# IPM_Circuit.net
KiCad netlist of a schematic drawn in Altium Designer
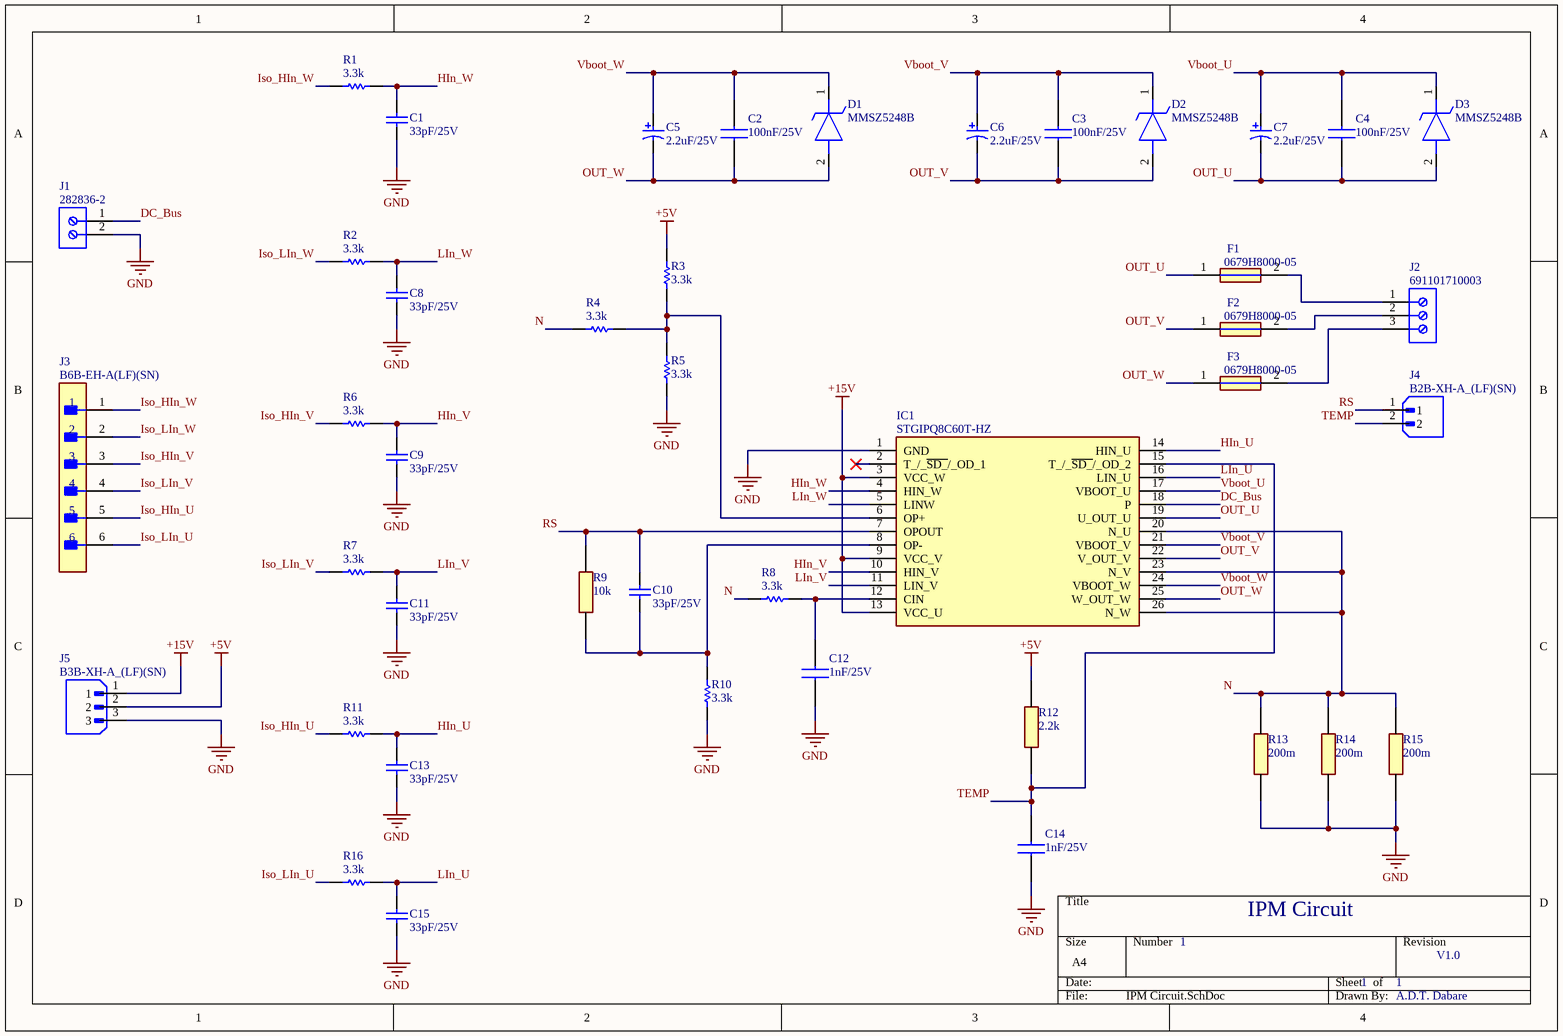
[diagram p0: IPM Circuit.SchDoc]

(export (version "E")
  (design (tool "Eeschema 10.0.6"))
  (components
    (comp (ref "C1")
      (value "33pF/25V")
      (footprint "CAPC1210(3225)100_N")
      (description "CAP 33pF 50V ±5% 1210 (3225 Metric) Thickness 1mm SMD")
      (fields (field (name "TOLERANCE") "Â±5%"))
      (libsource (lib "Altium Content Vault") (part "CAP"))
    )
    (comp (ref "C2")
      (value "100nF/25V")
      (footprint "SamacSys:CAPC3225X105N")
      (description "100nF 25V 1210 SMDCapacitor")
      (fields
        (field (name "MANUFACTURER_PART_NUMBER") "885012209015")
        (field (name "MOUSER PART NUMBER") "710-885012209015")
      )
      (libsource (lib "*") (part "885012209015"))
    )
    (comp (ref "C3")
      (value "100nF/25V")
      (footprint "SamacSys:CAPC3225X105N")
      (description "1nF 25V 1210 SMDCapacitor")
      (fields
        (field (name "MANUFACTURER_PART_NUMBER") "885012209015")
        (field (name "MOUSER PART NUMBER") "710-885012209015")
      )
      (libsource (lib "*") (part "885012209015"))
    )
    (comp (ref "C4")
      (value "100nF/25V")
      (footprint "SamacSys:CAPC3225X105N")
      (description "1nF 25V 1210 SMDCapacitor")
      (fields
        (field (name "MANUFACTURER_PART_NUMBER") "885012209015")
        (field (name "MOUSER PART NUMBER") "710-885012209015")
      )
      (libsource (lib "*") (part "885012209015"))
    )
    (comp (ref "C5")
      (value "2.2uF/25V")
      (footprint "CAPPR55-200-1100X500X1200")
      (description "Aluminum Electrolytic Capacitor, 2.2 uF, +/- 20%, 50 V, -40 to 85 degC, 2-Pin THD, RoHS, Bulk")
      (fields (field (name "VOLTAGE") "50V") (field (name "MANUFACTURER") "Panasonic"))
      (libsource (lib "Altium Content Vault") (part "CAP-P-2"))
    )
    (comp (ref "C6")
      (value "2.2uF/25V")
      (footprint "CAPPR55-200-1100X500X1200")
      (description "Aluminum Electrolytic Capacitor, 2.2 uF, +/- 20%, 50 V, -40 to 85 degC, 2-Pin THD, RoHS, Bulk")
      (fields (field (name "VOLTAGE") "50V") (field (name "MANUFACTURER") "Panasonic"))
      (libsource (lib "Altium Content Vault") (part "CAP-P-2"))
    )
    (comp (ref "C7")
      (value "2.2uF/25V")
      (footprint "CAPPR55-200-1100X500X1200")
      (description "Aluminum Electrolytic Capacitor, 2.2 uF, +/- 20%, 50 V, -40 to 85 degC, 2-Pin THD, RoHS, Bulk")
      (fields (field (name "VOLTAGE") "50V") (field (name "MANUFACTURER") "Panasonic"))
      (libsource (lib "Altium Content Vault") (part "CAP-P-2"))
    )
    (comp (ref "C8")
      (value "33pF/25V")
      (footprint "CAPC1210(3225)100_N")
      (description "CAP 33pF 50V ±5% 1210 (3225 Metric) Thickness 1mm SMD")
      (fields (field (name "TOLERANCE") "Â±5%"))
      (libsource (lib "Altium Content Vault") (part "CAP"))
    )
    (comp (ref "C9")
      (value "33pF/25V")
      (footprint "CAPC1210(3225)100_N")
      (description "CAP 33pF 50V ±5% 1210 (3225 Metric) Thickness 1mm SMD")
      (fields (field (name "TOLERANCE") "Â±5%"))
      (libsource (lib "Altium Content Vault") (part "CAP"))
    )
    (comp (ref "C10")
      (value "33pF/25V")
      (footprint "CAPC1210(3225)100_N")
      (description "CAP 33pF 50V ±5% 1210 (3225 Metric) Thickness 1mm SMD")
      (fields (field (name "TOLERANCE") "Â±5%"))
      (libsource (lib "Altium Content Vault") (part "CAP"))
    )
    (comp (ref "C11")
      (value "33pF/25V")
      (footprint "CAPC1210(3225)100_N")
      (description "CAP 33pF 50V ±5% 1210 (3225 Metric) Thickness 1mm SMD")
      (fields (field (name "TOLERANCE") "Â±5%"))
      (libsource (lib "Altium Content Vault") (part "CAP"))
    )
    (comp (ref "C12")
      (value "1nF/25V")
      (footprint "SamacSys:CAPC3225X105N")
      (description "1nF 25V 1210 SMDCapacitor")
      (fields
        (field (name "MANUFACTURER_PART_NUMBER") "885012209015")
        (field (name "MOUSER PART NUMBER") "710-885012209015")
      )
      (libsource (lib "*") (part "885012209015"))
    )
    (comp (ref "C13")
      (value "33pF/25V")
      (footprint "CAPC1210(3225)100_N")
      (description "CAP 33pF 50V ±5% 1210 (3225 Metric) Thickness 1mm SMD")
      (fields (field (name "TOLERANCE") "Â±5%"))
      (libsource (lib "Altium Content Vault") (part "CAP"))
    )
    (comp (ref "C14")
      (value "1nF/25V")
      (footprint "SamacSys:CAPC3225X105N")
      (description "1nF 25V 1210 SMDCapacitor")
      (fields
        (field (name "MANUFACTURER_PART_NUMBER") "885012209015")
        (field (name "MOUSER PART NUMBER") "710-885012209015")
      )
      (libsource (lib "*") (part "885012209015"))
    )
    (comp (ref "C15")
      (value "33pF/25V")
      (footprint "CAPC1210(3225)100_N")
      (description "CAP 33pF 50V ±5% 1210 (3225 Metric) Thickness 1mm SMD")
      (fields (field (name "TOLERANCE") "Â±5%"))
      (libsource (lib "Altium Content Vault") (part "CAP"))
    )
    (comp (ref "D1")
      (value "MMSZ5248B")
      (footprint "SamacSys:SOD3816X135N")
      (description "Diode")
      (fields
        (field (name "MANUFACTURER_PART_NUMBER") "MMSZ5248B_R1_00001")
        (field (name "MOUSER PART NUMBER") "241-MMSZ5248BR100001")
      )
      (libsource (lib "SamacSys") (part "MMSZ5248B_R1_00001"))
    )
    (comp (ref "D2")
      (value "MMSZ5248B")
      (footprint "SamacSys:SOD3816X135N")
      (description "Diode")
      (fields
        (field (name "MANUFACTURER_PART_NUMBER") "MMSZ5248B_R1_00001")
        (field (name "MOUSER PART NUMBER") "241-MMSZ5248BR100001")
      )
      (libsource (lib "SamacSys") (part "MMSZ5248B_R1_00001"))
    )
    (comp (ref "D3")
      (value "MMSZ5248B")
      (footprint "SamacSys:SOD3816X135N")
      (description "Diode")
      (fields
        (field (name "MANUFACTURER_PART_NUMBER") "MMSZ5248B_R1_00001")
        (field (name "MOUSER PART NUMBER") "241-MMSZ5248BR100001")
      )
      (libsource (lib "SamacSys") (part "MMSZ5248B_R1_00001"))
    )
    (comp (ref "F1")
      (value "0679H8000-05")
      (footprint "SamacSys:FUSC6125X279N")
      (description "Fuse")
      (libsource (lib "*") (part "0679H8000-05"))
    )
    (comp (ref "F2")
      (value "0679H8000-05")
      (footprint "SamacSys:FUSC6125X279N")
      (description "Fuse")
      (libsource (lib "*") (part "0679H8000-05"))
    )
    (comp (ref "F3")
      (value "0679H8000-05")
      (footprint "SamacSys:FUSC6125X279N")
      (description "Fuse")
      (libsource (lib "*") (part "0679H8000-05"))
    )
    (comp (ref "IC1")
      (value "STGIPQ8C60T-HZ")
      (footprint "SamacSys:STGIPQ5C60THZS")
      (description "Integrated Circuit")
      (fields (field (name "MOUSER PART NUMBER") "511-STGIPQ8C60T-HZ"))
      (libsource (lib "*") (part "STGIPQ8C60T-HZ"))
    )
    (comp (ref "J1")
      (value "282836-2")
      (footprint "TECO-282836-2_V")
      (description "Female Header, Pitch 5 mm, 1 x 2 Position, Height 10 mm, Tail Length 3.5 mm, Rohs, Bulk")
      (fields (field (name "VOLTAGE") "300V") (field (name "MANUFACTURER") "TE Connectivity"))
      (libsource (lib "Altium Content Vault") (part "CN-1P-F-TB2"))
    )
    (comp (ref "J2")
      (value "691101710003")
      (footprint "691101710003")
      (fields (field (name "VOLTAGE") "250V"))
      (libsource (lib "Altium Content Vault") (part "TBL - 1R - 03P - Screw"))
    )
    (comp (ref "J3")
      (value "B6B-EH-A(LF)(SN)")
      (footprint "FP-B6B-EH-A_LF_SN-MFG")
      (description "CONN HEADER VERT 6POS 2.5MM")
      (libsource (lib "Altium Content Vault") (part "f2cb566baf1c37ab5a3b8e90bbeafd6"))
    )
    (comp (ref "J4")
      (value "B2B-XH-A_(LF)(SN)")
      (footprint "JST_B2B-XH-A_(LF)(SN)")
      (description "Connector Header Through Hole 2 position 0.098 (2.50mm)")
      (fields (field (name "MF") "JST Sales") (field (name "MP") "B2B-XH-A (LF)(SN)"))
      (libsource (lib "B2B-XH-A__LF__SN_") (part "B2B-XH-A_(LF)(SN)"))
    )
    (comp (ref "J5")
      (value "B3B-XH-A_(LF)(SN)")
      (footprint "JST_B3B-XH-A (LF)(SN)")
      (description "Connector Header Through Hole 3 position 0.098 (2.50mm)")
      (fields (field (name "MF") "JST Sales America Inc.") (field (name "MP") "B3B-XH-A (LF)(SN)"))
      (libsource (lib "B3B-XH-A__LF__SN_") (part "B3B-XH-A_(LF)(SN)"))
    )
    (comp (ref "R1")
      (value "3.3k")
      (footprint "RESC3225X70X50NL20T20")
      (description "3.3k 0.5W 1210 SMD Resistor")
      (fields (field (name "PART NUMBER") "ERJ-L14KF10CU") (field (name "MANUFACTURER") "Panasonic"))
      (libsource (lib "Altium Content Vault") (part "RES"))
    )
    (comp (ref "R2")
      (value "3.3k")
      (footprint "RESC3225X70X50NL20T20")
      (description "3.3k 0.5W 1210 SMD Resistor")
      (fields (field (name "PART NUMBER") "ERJ-L14KF10CU") (field (name "MANUFACTURER") "Panasonic"))
      (libsource (lib "Altium Content Vault") (part "RES"))
    )
    (comp (ref "R3")
      (value "3.3k")
      (footprint "RESC3225X70X50NL20T20")
      (description "3.3k 0.5W 1210 SMD Resistor")
      (fields (field (name "PART NUMBER") "ERJ-L14KF10CU") (field (name "MANUFACTURER") "Panasonic"))
      (libsource (lib "Altium Content Vault") (part "RES"))
    )
    (comp (ref "R4")
      (value "3.3k")
      (footprint "RESC3225X70X50NL20T20")
      (description "3.3k 0.5W 1210 SMD Resistor")
      (fields (field (name "PART NUMBER") "ERJ-L14KF10CU") (field (name "MANUFACTURER") "Panasonic"))
      (libsource (lib "Altium Content Vault") (part "RES"))
    )
    (comp (ref "R5")
      (value "3.3k")
      (footprint "RESC3225X70X50NL20T20")
      (description "3.3k 0.5W 1210 SMD Resistor")
      (fields (field (name "PART NUMBER") "ERJ-L14KF10CU") (field (name "MANUFACTURER") "Panasonic"))
      (libsource (lib "Altium Content Vault") (part "RES"))
    )
    (comp (ref "R6")
      (value "3.3k")
      (footprint "RESC3225X70X50NL20T20")
      (description "3.3k 0.5W 1210 SMD Resistor")
      (fields (field (name "PART NUMBER") "ERJ-L14KF10CU") (field (name "MANUFACTURER") "Panasonic"))
      (libsource (lib "Altium Content Vault") (part "RES"))
    )
    (comp (ref "R7")
      (value "3.3k")
      (footprint "RESC3225X70X50NL20T20")
      (description "3.3k 0.5W 1210 SMD Resistor")
      (fields (field (name "PART NUMBER") "ERJ-L14KF10CU") (field (name "MANUFACTURER") "Panasonic"))
      (libsource (lib "Altium Content Vault") (part "RES"))
    )
    (comp (ref "R8")
      (value "3.3k")
      (footprint "RESC3225X70X50NL20T20")
      (description "3.3k 0.5W 1210 SMD Resistor")
      (fields (field (name "PART NUMBER") "ERJ-L14KF10CU") (field (name "MANUFACTURER") "Panasonic"))
      (libsource (lib "Altium Content Vault") (part "RES"))
    )
    (comp (ref "R9")
      (value "10k")
      (footprint "SamacSys:ERJ14BQF1R0U")
      (description "10k 0.5W 1210 SMD Resistor")
      (fields
        (field (name "MANUFACTURER_PART_NUMBER") "ERJ-14NF1002U")
        (field (name "MOUSER PART NUMBER") "667-ERJ-14NF1002U")
      )
      (libsource (lib "*") (part "ERJ-14NF1002U"))
    )
    (comp (ref "R10")
      (value "3.3k")
      (footprint "RESC3225X70X50NL20T20")
      (description "3.3k 0.5W 1210 SMD Resistor")
      (fields (field (name "PART NUMBER") "ERJ-L14KF10CU") (field (name "MANUFACTURER") "Panasonic"))
      (libsource (lib "Altium Content Vault") (part "RES"))
    )
    (comp (ref "R11")
      (value "3.3k")
      (footprint "RESC3225X70X50NL20T20")
      (description "3.3k 0.5W 1210 SMD Resistor")
      (fields (field (name "PART NUMBER") "ERJ-L14KF10CU") (field (name "MANUFACTURER") "Panasonic"))
      (libsource (lib "Altium Content Vault") (part "RES"))
    )
    (comp (ref "R12")
      (value "2.2k")
      (footprint "SamacSys:RESC3225X60N")
      (description "2.2k 0.5W 1210 SMD Resistor")
      (fields
        (field (name "MANUFACTURER_PART_NUMBER") "CRCW12102K20JNEA")
        (field (name "MOUSER PART NUMBER") "71-CRCW1210J-2.2K-E3")
      )
      (libsource (lib "*") (part "CRCW12102K20JNEA"))
    )
    (comp (ref "R13")
      (value "200m")
      (footprint "SamacSys:RESC6432X90N")
      (description "0.2Ohm 3W 2512 SMD Resistor")
      (fields
        (field (name "MANUFACTURER_PART_NUMBER") "TLRP3A30CR200FTE")
        (field (name "MOUSER PART NUMBER") "279-TLRP3A30CR200FTE")
      )
      (libsource (lib "*") (part "TLRP3A30CR200FTE"))
    )
    (comp (ref "R14")
      (value "200m")
      (footprint "SamacSys:RESC6432X90N")
      (description "0.2Ohm 3W 2512 SMD Resistor")
      (fields
        (field (name "MANUFACTURER_PART_NUMBER") "TLRP3A30CR200FTE")
        (field (name "MOUSER PART NUMBER") "279-TLRP3A30CR200FTE")
      )
      (libsource (lib "*") (part "TLRP3A30CR200FTE"))
    )
    (comp (ref "R15")
      (value "200m")
      (footprint "SamacSys:RESC6432X90N")
      (description "0.2Ohm 3W 2512 SMD Resistor")
      (fields
        (field (name "MANUFACTURER_PART_NUMBER") "TLRP3A30CR200FTE")
        (field (name "MOUSER PART NUMBER") "279-TLRP3A30CR200FTE")
      )
      (libsource (lib "*") (part "TLRP3A30CR200FTE"))
    )
    (comp (ref "R16")
      (value "3.3k")
      (footprint "RESC3225X70X50NL20T20")
      (description "3.3k 0.5W 1210 SMD Resistor")
      (fields (field (name "PART NUMBER") "ERJ-L14KF10CU") (field (name "MANUFACTURER") "Panasonic"))
      (libsource (lib "Altium Content Vault") (part "RES"))
    )
  )
  (nets
    (net (code "1") (name "+5V") (class "Default")
      (node (ref "J5") (pin "2") (pinfunction "2_2") (pintype "passive"))
      (node (ref "R12") (pin "2") (pinfunction "2_2") (pintype "passive"))
      (node (ref "R3") (pin "1") (pinfunction "1_1") (pintype "passive"))
    )
    (net (code "2") (name "+15V") (class "Default")
      (node (ref "IC1") (pin "13") (pinfunction "VCC_U_13") (pintype "passive"))
      (node (ref "IC1") (pin "3") (pinfunction "VCC_W_3") (pintype "passive"))
      (node (ref "IC1") (pin "9") (pinfunction "VCC_V_9") (pintype "passive"))
      (node (ref "J5") (pin "1") (pinfunction "1_1") (pintype "passive"))
    )
    (net (code "3") (name "/DC_Bus") (class "Default")
      (node (ref "IC1") (pin "18") (pinfunction "P_18") (pintype "passive"))
      (node (ref "J1") (pin "1") (pinfunction "1_1") (pintype "passive"))
    )
    (net (code "4") (name "/HIn_U") (class "Default")
      (node (ref "C13") (pin "1") (pinfunction "1_1") (pintype "passive"))
      (node (ref "IC1") (pin "14") (pinfunction "HIN_U_14") (pintype "passive"))
      (node (ref "R11") (pin "1") (pinfunction "1_1") (pintype "passive"))
    )
    (net (code "5") (name "/HIn_V") (class "Default")
      (node (ref "C9") (pin "1") (pinfunction "1_1") (pintype "passive"))
      (node (ref "IC1") (pin "10") (pinfunction "HIN_V_10") (pintype "passive"))
      (node (ref "R6") (pin "1") (pinfunction "1_1") (pintype "passive"))
    )
    (net (code "6") (name "/HIn_W") (class "Default")
      (node (ref "C1") (pin "1") (pinfunction "1_1") (pintype "passive"))
      (node (ref "IC1") (pin "4") (pinfunction "HIN_W_4") (pintype "passive"))
      (node (ref "R1") (pin "1") (pinfunction "1_1") (pintype "passive"))
    )
    (net (code "7") (name "/Iso_HIn_U") (class "Default")
      (node (ref "J3") (pin "5") (pinfunction "5_5") (pintype "passive"))
      (node (ref "R11") (pin "2") (pinfunction "2_2") (pintype "passive"))
    )
    (net (code "8") (name "/Iso_HIn_V") (class "Default")
      (node (ref "J3") (pin "3") (pinfunction "3_3") (pintype "passive"))
      (node (ref "R6") (pin "2") (pinfunction "2_2") (pintype "passive"))
    )
    (net (code "9") (name "/Iso_HIn_W") (class "Default")
      (node (ref "J3") (pin "1") (pinfunction "1_1") (pintype "passive"))
      (node (ref "R1") (pin "2") (pinfunction "2_2") (pintype "passive"))
    )
    (net (code "10") (name "/Iso_LIn_U") (class "Default")
      (node (ref "J3") (pin "6") (pinfunction "6_6") (pintype "passive"))
      (node (ref "R16") (pin "2") (pinfunction "2_2") (pintype "passive"))
    )
    (net (code "11") (name "/Iso_LIn_V") (class "Default")
      (node (ref "J3") (pin "4") (pinfunction "4_4") (pintype "passive"))
      (node (ref "R7") (pin "2") (pinfunction "2_2") (pintype "passive"))
    )
    (net (code "12") (name "/Iso_LIn_W") (class "Default")
      (node (ref "J3") (pin "2") (pinfunction "2_2") (pintype "passive"))
      (node (ref "R2") (pin "2") (pinfunction "2_2") (pintype "passive"))
    )
    (net (code "13") (name "/LIn_U") (class "Default")
      (node (ref "C15") (pin "1") (pinfunction "1_1") (pintype "passive"))
      (node (ref "IC1") (pin "16") (pinfunction "LIN_U_16") (pintype "passive"))
      (node (ref "R16") (pin "1") (pinfunction "1_1") (pintype "passive"))
    )
    (net (code "14") (name "/LIn_V") (class "Default")
      (node (ref "C11") (pin "1") (pinfunction "1_1") (pintype "passive"))
      (node (ref "IC1") (pin "11") (pinfunction "LIN_V_11") (pintype "passive"))
      (node (ref "R7") (pin "1") (pinfunction "1_1") (pintype "passive"))
    )
    (net (code "15") (name "/LIn_W") (class "Default")
      (node (ref "C8") (pin "1") (pinfunction "1_1") (pintype "passive"))
      (node (ref "IC1") (pin "5") (pinfunction "LINW_5") (pintype "passive"))
      (node (ref "R2") (pin "1") (pinfunction "1_1") (pintype "passive"))
    )
    (net (code "16") (name "/N") (class "Default")
      (node (ref "IC1") (pin "20") (pinfunction "N_U_20") (pintype "passive"))
      (node (ref "IC1") (pin "23") (pinfunction "N_V_23") (pintype "passive"))
      (node (ref "IC1") (pin "26") (pinfunction "N_W_26") (pintype "passive"))
      (node (ref "R13") (pin "2") (pinfunction "2_2") (pintype "passive"))
      (node (ref "R14") (pin "2") (pinfunction "2_2") (pintype "passive"))
      (node (ref "R15") (pin "2") (pinfunction "2_2") (pintype "passive"))
      (node (ref "R4") (pin "2") (pinfunction "2_2") (pintype "passive"))
      (node (ref "R8") (pin "2") (pinfunction "2_2") (pintype "passive"))
    )
    (net (code "17") (name "/OUT_U") (class "Default")
      (node (ref "C4") (pin "1") (pinfunction "1_1") (pintype "passive"))
      (node (ref "C7") (pin "2") (pinfunction "2_2") (pintype "passive"))
      (node (ref "D3") (pin "2") (pinfunction "A_2") (pintype "passive"))
      (node (ref "F1") (pin "1") (pinfunction "1_1") (pintype "passive"))
      (node (ref "IC1") (pin "19") (pinfunction "U_OUT_U_19") (pintype "passive"))
    )
    (net (code "18") (name "/OUT_V") (class "Default")
      (node (ref "C3") (pin "1") (pinfunction "1_1") (pintype "passive"))
      (node (ref "C6") (pin "2") (pinfunction "2_2") (pintype "passive"))
      (node (ref "D2") (pin "2") (pinfunction "A_2") (pintype "passive"))
      (node (ref "F2") (pin "1") (pinfunction "1_1") (pintype "passive"))
      (node (ref "IC1") (pin "22") (pinfunction "V_OUT_V_22") (pintype "passive"))
    )
    (net (code "19") (name "/OUT_W") (class "Default")
      (node (ref "C2") (pin "1") (pinfunction "1_1") (pintype "passive"))
      (node (ref "C5") (pin "2") (pinfunction "2_2") (pintype "passive"))
      (node (ref "D1") (pin "2") (pinfunction "A_2") (pintype "passive"))
      (node (ref "F3") (pin "1") (pinfunction "1_1") (pintype "passive"))
      (node (ref "IC1") (pin "25") (pinfunction "W_OUT_W_25") (pintype "passive"))
    )
    (net (code "20") (name "/RS") (class "Default")
      (node (ref "C10") (pin "1") (pinfunction "1_1") (pintype "passive"))
      (node (ref "IC1") (pin "7") (pinfunction "OPOUT_7") (pintype "passive"))
      (node (ref "J4") (pin "1") (pinfunction "1_1") (pintype "passive"))
      (node (ref "R9") (pin "2") (pinfunction "2_2") (pintype "passive"))
    )
    (net (code "21") (name "/TEMP") (class "Default")
      (node (ref "C14") (pin "2") (pinfunction "2_2") (pintype "passive"))
      (node (ref "IC1") (pin "15") (pinfunction "T_/_~{SD_}/_OD_2_15") (pintype "passive"))
      (node (ref "J4") (pin "2") (pinfunction "2_2") (pintype "passive"))
      (node (ref "R12") (pin "1") (pinfunction "1_1") (pintype "passive"))
    )
    (net (code "22") (name "/Vboot_U") (class "Default")
      (node (ref "C4") (pin "2") (pinfunction "2_2") (pintype "passive"))
      (node (ref "C7") (pin "1") (pinfunction "1_1") (pintype "passive"))
      (node (ref "D3") (pin "1") (pinfunction "K_1") (pintype "passive"))
      (node (ref "IC1") (pin "17") (pinfunction "VBOOT_U_17") (pintype "passive"))
    )
    (net (code "23") (name "/Vboot_V") (class "Default")
      (node (ref "C3") (pin "2") (pinfunction "2_2") (pintype "passive"))
      (node (ref "C6") (pin "1") (pinfunction "1_1") (pintype "passive"))
      (node (ref "D2") (pin "1") (pinfunction "K_1") (pintype "passive"))
      (node (ref "IC1") (pin "21") (pinfunction "VBOOT_V_21") (pintype "passive"))
    )
    (net (code "24") (name "/Vboot_W") (class "Default")
      (node (ref "C2") (pin "2") (pinfunction "2_2") (pintype "passive"))
      (node (ref "C5") (pin "1") (pinfunction "1_1") (pintype "passive"))
      (node (ref "D1") (pin "1") (pinfunction "K_1") (pintype "passive"))
      (node (ref "IC1") (pin "24") (pinfunction "VBOOT_W_24") (pintype "passive"))
    )
    (net (code "25") (name "GND") (class "Default")
      (node (ref "C1") (pin "2") (pinfunction "2_2") (pintype "passive"))
      (node (ref "C11") (pin "2") (pinfunction "2_2") (pintype "passive"))
      (node (ref "C12") (pin "1") (pinfunction "1_1") (pintype "passive"))
      (node (ref "C13") (pin "2") (pinfunction "2_2") (pintype "passive"))
      (node (ref "C14") (pin "1") (pinfunction "1_1") (pintype "passive"))
      (node (ref "C15") (pin "2") (pinfunction "2_2") (pintype "passive"))
      (node (ref "C8") (pin "2") (pinfunction "2_2") (pintype "passive"))
      (node (ref "C9") (pin "2") (pinfunction "2_2") (pintype "passive"))
      (node (ref "IC1") (pin "1") (pinfunction "GND_1") (pintype "passive"))
      (node (ref "J1") (pin "2") (pinfunction "2_2") (pintype "passive"))
      (node (ref "J5") (pin "3") (pinfunction "3_3") (pintype "passive"))
      (node (ref "R10") (pin "2") (pinfunction "2_2") (pintype "passive"))
      (node (ref "R13") (pin "1") (pinfunction "1_1") (pintype "passive"))
      (node (ref "R14") (pin "1") (pinfunction "1_1") (pintype "passive"))
      (node (ref "R15") (pin "1") (pinfunction "1_1") (pintype "passive"))
      (node (ref "R5") (pin "2") (pinfunction "2_2") (pintype "passive"))
    )
    (net (code "26") (name "Net-(F1-Pad2)") (class "Default")
      (node (ref "F1") (pin "2") (pinfunction "2_2") (pintype "passive"))
      (node (ref "J2") (pin "1") (pinfunction "1_1") (pintype "passive"))
    )
    (net (code "27") (name "Net-(F2-Pad2)") (class "Default")
      (node (ref "F2") (pin "2") (pinfunction "2_2") (pintype "passive"))
      (node (ref "J2") (pin "2") (pinfunction "2_2") (pintype "passive"))
    )
    (net (code "28") (name "Net-(F3-Pad2)") (class "Default")
      (node (ref "F3") (pin "2") (pinfunction "2_2") (pintype "passive"))
      (node (ref "J2") (pin "3") (pinfunction "3_3") (pintype "passive"))
    )
    (net (code "29") (name "Net-(IC1-CIN)") (class "Default")
      (node (ref "C12") (pin "2") (pinfunction "2_2") (pintype "passive"))
      (node (ref "IC1") (pin "12") (pinfunction "CIN_12") (pintype "passive"))
      (node (ref "R8") (pin "1") (pinfunction "1_1") (pintype "passive"))
    )
    (net (code "30") (name "Net-(IC1-OP+)") (class "Default")
      (node (ref "IC1") (pin "6") (pinfunction "OP+_6") (pintype "passive"))
      (node (ref "R3") (pin "2") (pinfunction "2_2") (pintype "passive"))
      (node (ref "R4") (pin "1") (pinfunction "1_1") (pintype "passive"))
      (node (ref "R5") (pin "1") (pinfunction "1_1") (pintype "passive"))
    )
    (net (code "31") (name "Net-(IC1-OP-)") (class "Default")
      (node (ref "C10") (pin "2") (pinfunction "2_2") (pintype "passive"))
      (node (ref "IC1") (pin "8") (pinfunction "OP-_8") (pintype "passive"))
      (node (ref "R10") (pin "1") (pinfunction "1_1") (pintype "passive"))
      (node (ref "R9") (pin "1") (pinfunction "1_1") (pintype "passive"))
    )
    (net (code "32") (name "unconnected-(IC1-T_{slash}_~{SD_}{slash}_OD_1-Pad2)") (class "Default")
      (node (ref "IC1") (pin "2") (pinfunction "T_/_~{SD_}/_OD_1_2") (pintype "passive+no_connect"))
    )
  )
)
